# TwoMotorController_1_0.net
KiCad netlist of a schematic drawn in EAGLE
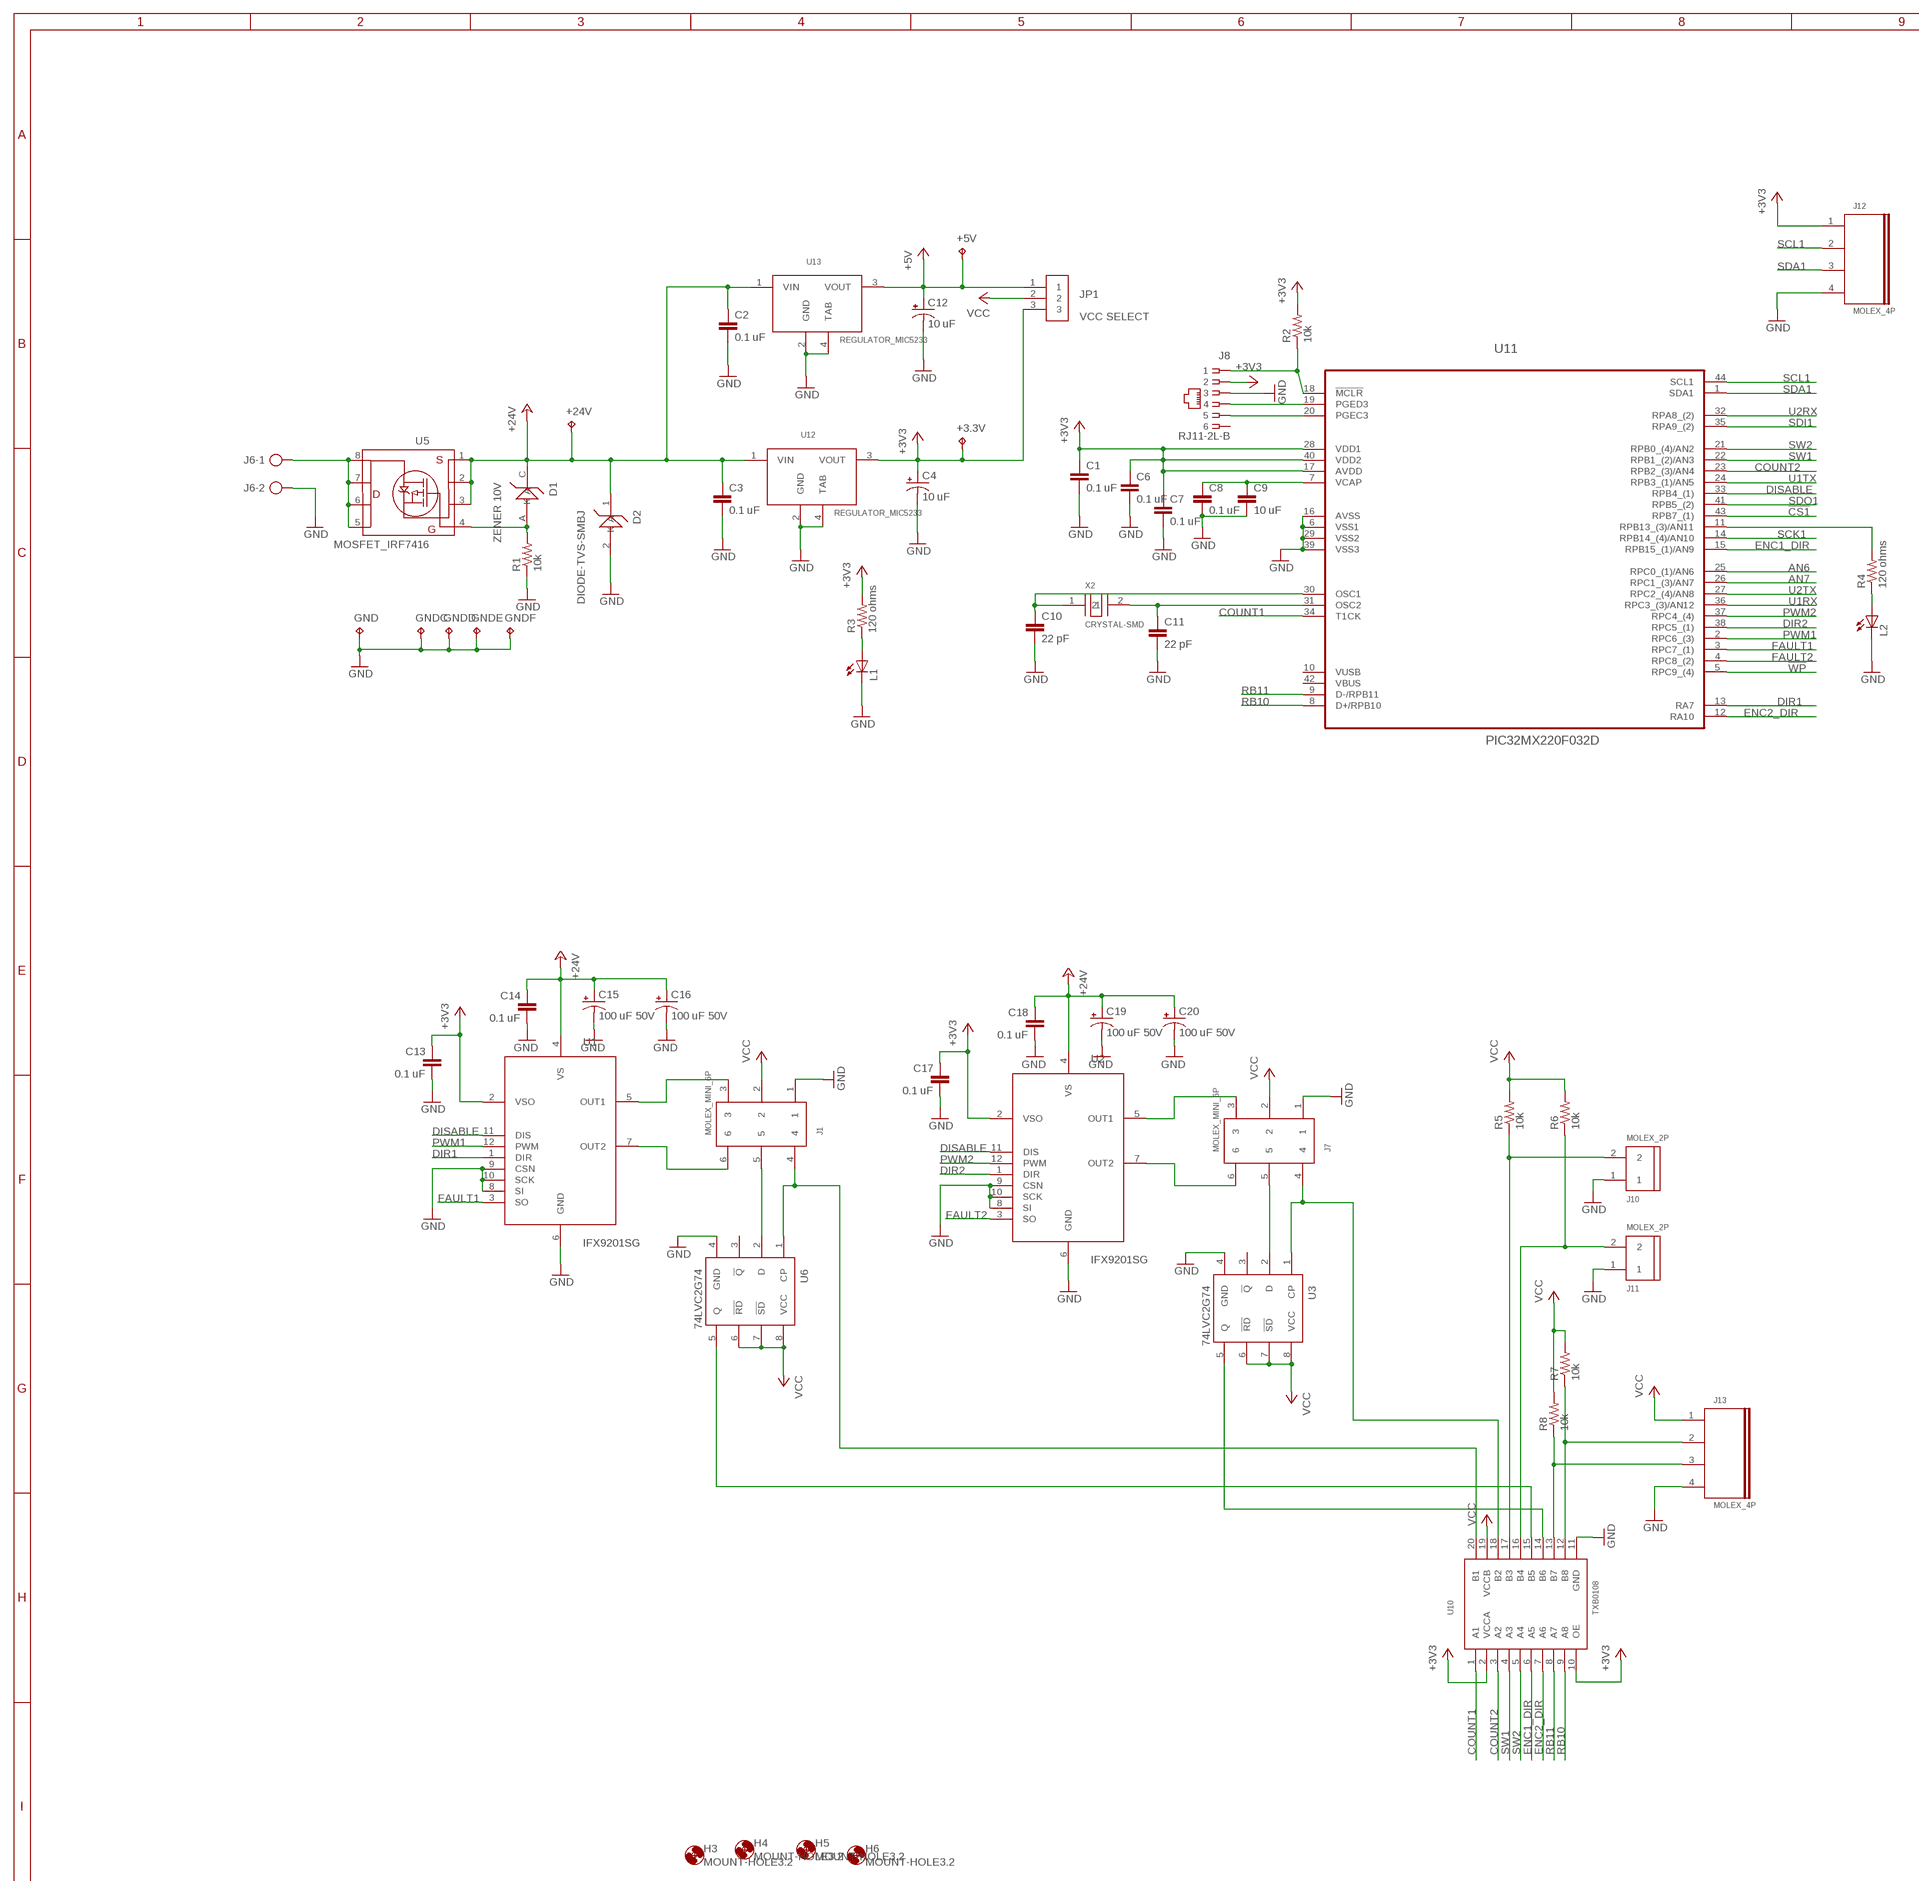
[diagram p0: schematic, sheet 1, part 1 of 2]
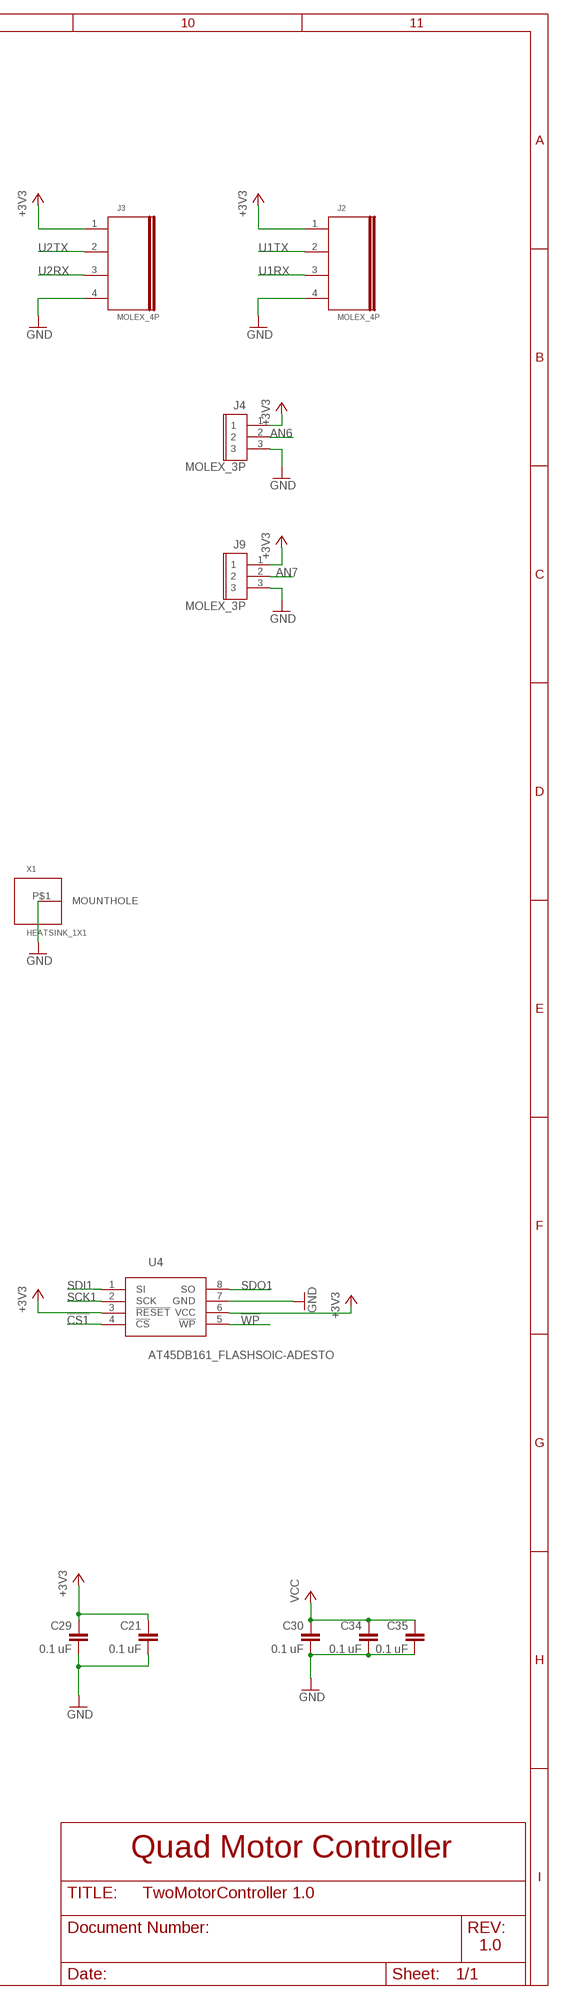
[diagram p1: schematic, sheet 1, part 2 of 2]

(export (version "E")
  (design (tool "Eeschema 10.0.6"))
  (components
    (comp (ref "+3.3V")
      (value "TP")
      (footprint "eagle-import:TESTPAD")
      (libsource (lib "eagle-import") (part "TP"))
    )
    (comp (ref "+5V")
      (value "TP")
      (footprint "eagle-import:TESTPAD")
      (libsource (lib "eagle-import") (part "TP"))
    )
    (comp (ref "+24V")
      (value "TP")
      (footprint "eagle-import:TESTPAD")
      (libsource (lib "eagle-import") (part "TP"))
    )
    (comp (ref "C1")
      (value "0.1 uF")
      (footprint "eagle-import:C0805")
      (libsource (lib "eagle-import") (part "C0805"))
    )
    (comp (ref "C2")
      (value "0.1 uF")
      (footprint "eagle-import:C0805")
      (libsource (lib "eagle-import") (part "C0805"))
    )
    (comp (ref "C3")
      (value "0.1 uF")
      (footprint "eagle-import:C0805")
      (libsource (lib "eagle-import") (part "C0805"))
    )
    (comp (ref "C4")
      (value "10 uF")
      (footprint "eagle-import:POLCAP_2MM")
      (libsource (lib "eagle-import") (part "POLCAPE2-5"))
    )
    (comp (ref "C6")
      (value "0.1 uF")
      (footprint "eagle-import:C0805")
      (libsource (lib "eagle-import") (part "C0805"))
    )
    (comp (ref "C7")
      (value "0.1 uF")
      (footprint "eagle-import:C0805")
      (libsource (lib "eagle-import") (part "C0805"))
    )
    (comp (ref "C8")
      (value "0.1 uF")
      (footprint "eagle-import:C0805")
      (libsource (lib "eagle-import") (part "C0805"))
    )
    (comp (ref "C9")
      (value "10 uF")
      (footprint "eagle-import:C0805")
      (libsource (lib "eagle-import") (part "C0805"))
    )
    (comp (ref "C10")
      (value "22 pF")
      (footprint "eagle-import:C0805")
      (libsource (lib "eagle-import") (part "C0805"))
    )
    (comp (ref "C11")
      (value "22 pF")
      (footprint "eagle-import:C0805")
      (libsource (lib "eagle-import") (part "C0805"))
    )
    (comp (ref "C12")
      (value "10 uF")
      (footprint "eagle-import:POLCAP_2MM")
      (libsource (lib "eagle-import") (part "POLCAPE2-5"))
    )
    (comp (ref "C13")
      (value "0.1 uF")
      (footprint "eagle-import:C0805")
      (libsource (lib "eagle-import") (part "C0805"))
    )
    (comp (ref "C14")
      (value "0.1 uF")
      (footprint "eagle-import:C0805")
      (libsource (lib "eagle-import") (part "C0805"))
    )
    (comp (ref "C15")
      (value "100 uF 50V")
      (footprint "eagle-import:E3,5-10")
      (libsource (lib "eagle-import") (part "POLCAPE3.5-10"))
    )
    (comp (ref "C16")
      (value "100 uF 50V")
      (footprint "eagle-import:E3,5-10")
      (libsource (lib "eagle-import") (part "POLCAPE3.5-10"))
    )
    (comp (ref "C17")
      (value "0.1 uF")
      (footprint "eagle-import:C0805")
      (libsource (lib "eagle-import") (part "C0805"))
    )
    (comp (ref "C18")
      (value "0.1 uF")
      (footprint "eagle-import:C0805")
      (libsource (lib "eagle-import") (part "C0805"))
    )
    (comp (ref "C19")
      (value "100 uF 50V")
      (footprint "eagle-import:E3,5-10")
      (libsource (lib "eagle-import") (part "POLCAPE3.5-10"))
    )
    (comp (ref "C20")
      (value "100 uF 50V")
      (footprint "eagle-import:E3,5-10")
      (libsource (lib "eagle-import") (part "POLCAPE3.5-10"))
    )
    (comp (ref "C21")
      (value "0.1 uF")
      (footprint "eagle-import:C0805")
      (libsource (lib "eagle-import") (part "C0805"))
    )
    (comp (ref "C29")
      (value "0.1 uF")
      (footprint "eagle-import:C0805")
      (libsource (lib "eagle-import") (part "C0805"))
    )
    (comp (ref "C30")
      (value "0.1 uF")
      (footprint "eagle-import:C0805")
      (libsource (lib "eagle-import") (part "C0805"))
    )
    (comp (ref "C34")
      (value "0.1 uF")
      (footprint "eagle-import:C0805")
      (libsource (lib "eagle-import") (part "C0805"))
    )
    (comp (ref "C35")
      (value "0.1 uF")
      (footprint "eagle-import:C0805")
      (libsource (lib "eagle-import") (part "C0805"))
    )
    (comp (ref "D1")
      (value "ZENER 10V")
      (footprint "eagle-import:DO-214AC")
      (libsource (lib "eagle-import") (part "DIODE-ZENERDO-214AC"))
    )
    (comp (ref "D2")
      (value "DIODE-TVS-SMBJ")
      (footprint "eagle-import:DIODE-TVS-SMBJ")
      (libsource (lib "eagle-import") (part "DIODE-TVS-SMBJ"))
    )
    (comp (ref "GND")
      (value "TP")
      (footprint "eagle-import:TESTPAD")
      (libsource (lib "eagle-import") (part "TP"))
    )
    (comp (ref "GNDC")
      (value "TP")
      (footprint "eagle-import:TESTPAD")
      (libsource (lib "eagle-import") (part "TP"))
    )
    (comp (ref "GNDD")
      (value "TP")
      (footprint "eagle-import:TESTPAD")
      (libsource (lib "eagle-import") (part "TP"))
    )
    (comp (ref "GNDE")
      (value "TP")
      (footprint "eagle-import:TESTPAD")
      (libsource (lib "eagle-import") (part "TP"))
    )
    (comp (ref "GNDF")
      (value "TP")
      (footprint "eagle-import:TESTPAD")
      (libsource (lib "eagle-import") (part "TP"))
    )
    (comp (ref "H3")
      (value "MOUNT-HOLE3.2")
      (footprint "eagle-import:3,2")
      (libsource (lib "eagle-import") (part "MOUNT-HOLE3.2"))
    )
    (comp (ref "H4")
      (value "MOUNT-HOLE3.2")
      (footprint "eagle-import:3,2")
      (libsource (lib "eagle-import") (part "MOUNT-HOLE3.2"))
    )
    (comp (ref "H5")
      (value "MOUNT-HOLE3.2")
      (footprint "eagle-import:3,2")
      (libsource (lib "eagle-import") (part "MOUNT-HOLE3.2"))
    )
    (comp (ref "H6")
      (value "MOUNT-HOLE3.2")
      (footprint "eagle-import:3,2")
      (libsource (lib "eagle-import") (part "MOUNT-HOLE3.2"))
    )
    (comp (ref "J1")
      (value "MOLEX_MINI_6P")
      (footprint "eagle-import:MOLEX_MINI_6P")
      (libsource (lib "eagle-import") (part "MOLEX_MINI_6P"))
    )
    (comp (ref "J2")
      (value "MOLEX_4P")
      (footprint "eagle-import:MOLEX_4P")
      (libsource (lib "eagle-import") (part "MOLEX_4P"))
    )
    (comp (ref "J3")
      (value "MOLEX_4P")
      (footprint "eagle-import:MOLEX_4P")
      (libsource (lib "eagle-import") (part "MOLEX_4P"))
    )
    (comp (ref "J4")
      (value "MOLEX_3P")
      (footprint "eagle-import:MOLEX_3P")
      (libsource (lib "eagle-import") (part "MOLEX_3P"))
    )
    (comp (ref "J6")
      (value "TRMBLOCK_5MM_2P")
      (footprint "eagle-import:TRMBLOCK_5MM_2P")
      (libsource (lib "eagle-import") (part "TRMBLOCK_5MM_2P"))
    )
    (comp (ref "J7")
      (value "MOLEX_MINI_6P")
      (footprint "eagle-import:MOLEX_MINI_6P")
      (libsource (lib "eagle-import") (part "MOLEX_MINI_6P"))
    )
    (comp (ref "J8")
      (value "RJ11-2L-B")
      (footprint "eagle-import:RJ11-NO_SHIELD")
      (fields (field (name "MF") "TYCO ELECTRONICS"))
      (libsource (lib "eagle-import") (part "RJ11-2L-B"))
    )
    (comp (ref "J9")
      (value "MOLEX_3P")
      (footprint "eagle-import:MOLEX_3P")
      (libsource (lib "eagle-import") (part "MOLEX_3P"))
    )
    (comp (ref "J10")
      (value "MOLEX_2P")
      (footprint "eagle-import:MOLEX_2P")
      (libsource (lib "eagle-import") (part "MOLEX_2P"))
    )
    (comp (ref "J11")
      (value "MOLEX_2P")
      (footprint "eagle-import:MOLEX_2P")
      (libsource (lib "eagle-import") (part "MOLEX_2P"))
    )
    (comp (ref "J12")
      (value "MOLEX_4P")
      (footprint "eagle-import:MOLEX_4P")
      (libsource (lib "eagle-import") (part "MOLEX_4P"))
    )
    (comp (ref "J13")
      (value "MOLEX_4P")
      (footprint "eagle-import:MOLEX_4P")
      (libsource (lib "eagle-import") (part "MOLEX_4P"))
    )
    (comp (ref "JP1")
      (value "VCC SELECT")
      (footprint "eagle-import:JUMPER_3P")
      (libsource (lib "eagle-import") (part "JUMPER_3P"))
    )
    (comp (ref "L1")
      (value "LED5MM")
      (footprint "eagle-import:LED5MM")
      (libsource (lib "eagle-import") (part "LED5MM"))
    )
    (comp (ref "L2")
      (value "LED5MM")
      (footprint "eagle-import:LED5MM")
      (libsource (lib "eagle-import") (part "LED5MM"))
    )
    (comp (ref "R1")
      (value "10k")
      (footprint "eagle-import:R0805")
      (libsource (lib "eagle-import") (part "RESISTORR0805"))
    )
    (comp (ref "R2")
      (value "10k")
      (footprint "eagle-import:R0805")
      (libsource (lib "eagle-import") (part "RESISTORR0805"))
    )
    (comp (ref "R3")
      (value "120 ohms")
      (footprint "eagle-import:R0805")
      (libsource (lib "eagle-import") (part "RESISTORR0805"))
    )
    (comp (ref "R4")
      (value "120 ohms")
      (footprint "eagle-import:R0805")
      (libsource (lib "eagle-import") (part "RESISTORR0805"))
    )
    (comp (ref "R5")
      (value "10k")
      (footprint "eagle-import:R0805")
      (libsource (lib "eagle-import") (part "RESISTORR0805"))
    )
    (comp (ref "R6")
      (value "10k")
      (footprint "eagle-import:R0805")
      (libsource (lib "eagle-import") (part "RESISTORR0805"))
    )
    (comp (ref "R7")
      (value "10k")
      (footprint "eagle-import:R0805")
      (libsource (lib "eagle-import") (part "RESISTORR0805"))
    )
    (comp (ref "R8")
      (value "10k")
      (footprint "eagle-import:R0805")
      (libsource (lib "eagle-import") (part "RESISTORR0805"))
    )
    (comp (ref "U1")
      (value "IFX9201SG")
      (footprint "eagle-import:IFX9201SG")
      (libsource (lib "eagle-import") (part "IFX9201SG"))
    )
    (comp (ref "U2")
      (value "IFX9201SG")
      (footprint "eagle-import:IFX9201SG")
      (libsource (lib "eagle-import") (part "IFX9201SG"))
    )
    (comp (ref "U3")
      (value "74LVC2G74")
      (footprint "eagle-import:TSSOP8")
      (libsource (lib "eagle-import") (part "74LVC2G74"))
    )
    (comp (ref "U4")
      (value "AT45DB161_FLASHSOIC-ADESTO")
      (footprint "eagle-import:SOIC-ADESTO")
      (libsource (lib "eagle-import") (part "AT45DB161_FLASHSOIC-ADESTO"))
    )
    (comp (ref "U5")
      (value "MOSFET_IRF7416")
      (footprint "eagle-import:SO-8-3.9MM")
      (libsource (lib "eagle-import") (part "MOSFET_IRF7416"))
    )
    (comp (ref "U6")
      (value "74LVC2G74")
      (footprint "eagle-import:TSSOP8")
      (libsource (lib "eagle-import") (part "74LVC2G74"))
    )
    (comp (ref "U10")
      (value "TXB0108")
      (footprint "eagle-import:TSSOP20")
      (libsource (lib "eagle-import") (part "TXB0108"))
    )
    (comp (ref "U11")
      (value "PIC32MX220F032D")
      (footprint "eagle-import:QFP80P1200X1200X120-44N")
      (fields (field (name "MPN") "PIC18F4550-I/PT"))
      (libsource (lib "eagle-import") (part "PIC32MX220F032D"))
    )
    (comp (ref "U12")
      (value "REGULATOR_MIC5233")
      (footprint "eagle-import:REGULATOR_MIC5233")
      (libsource (lib "eagle-import") (part "REGULATOR_MIC5233"))
    )
    (comp (ref "U13")
      (value "REGULATOR_MIC5233")
      (footprint "eagle-import:REGULATOR_MIC5233")
      (libsource (lib "eagle-import") (part "REGULATOR_MIC5233"))
    )
    (comp (ref "X1")
      (value "HEATSINK_1X1")
      (footprint "eagle-import:HEATSINK_1X1")
      (libsource (lib "eagle-import") (part "HEATSINK_1X1"))
    )
    (comp (ref "X2")
      (value "CRYSTAL-SMD")
      (footprint "eagle-import:CRYSTAL-SMD")
      (libsource (lib "eagle-import") (part "CRYSTAL-SMD"))
    )
  )
  (nets
    (net (code "1") (name "+3V3") (class "Default")
      (node (ref "+3.3V") (pin "P$1") (pinfunction "TP_P$1") (pintype "input"))
      (node (ref "C1") (pin "1") (pinfunction "1_1") (pintype "passive"))
      (node (ref "C13") (pin "1") (pinfunction "1_1") (pintype "passive"))
      (node (ref "C17") (pin "1") (pinfunction "1_1") (pintype "passive"))
      (node (ref "C21") (pin "1") (pinfunction "1_1") (pintype "passive"))
      (node (ref "C29") (pin "1") (pinfunction "1_1") (pintype "passive"))
      (node (ref "C4") (pin "+") (pinfunction "+_+") (pintype "passive"))
      (node (ref "C6") (pin "1") (pinfunction "1_1") (pintype "passive"))
      (node (ref "C7") (pin "1") (pinfunction "1_1") (pintype "passive"))
      (node (ref "J12") (pin "1") (pinfunction "1_1") (pintype "bidirectional"))
      (node (ref "J2") (pin "1") (pinfunction "1_1") (pintype "bidirectional"))
      (node (ref "J3") (pin "1") (pinfunction "1_1") (pintype "bidirectional"))
      (node (ref "J4") (pin "1") (pinfunction "1_1") (pintype "bidirectional"))
      (node (ref "J8") (pin "2") (pinfunction "2_2") (pintype "passive"))
      (node (ref "J9") (pin "1") (pinfunction "1_1") (pintype "bidirectional"))
      (node (ref "JP1") (pin "3") (pinfunction "3_3") (pintype "bidirectional"))
      (node (ref "R2") (pin "2") (pinfunction "2_2") (pintype "passive"))
      (node (ref "R3") (pin "2") (pinfunction "2_2") (pintype "passive"))
      (node (ref "U1") (pin "2") (pinfunction "VSO_2") (pintype "bidirectional"))
      (node (ref "U10") (pin "10") (pinfunction "OE_10") (pintype "bidirectional"))
      (node (ref "U10") (pin "2") (pinfunction "VCCA_2") (pintype "bidirectional"))
      (node (ref "U11") (pin "17") (pinfunction "AVDD_17") (pintype "power_in"))
      (node (ref "U11") (pin "28") (pinfunction "VDD1_28") (pintype "power_in"))
      (node (ref "U11") (pin "40") (pinfunction "VDD2_40") (pintype "input"))
      (node (ref "U12") (pin "3") (pinfunction "VOUT_3") (pintype "power_in"))
      (node (ref "U2") (pin "2") (pinfunction "VSO_2") (pintype "bidirectional"))
      (node (ref "U4") (pin "3") (pinfunction "~{RESET}_3") (pintype "input"))
      (node (ref "U4") (pin "6") (pinfunction "VCC_6") (pintype "power_in"))
    )
    (net (code "2") (name "+5V") (class "Default")
      (node (ref "+5V") (pin "P$1") (pinfunction "TP_P$1") (pintype "input"))
      (node (ref "C12") (pin "+") (pinfunction "+_+") (pintype "passive"))
      (node (ref "JP1") (pin "1") (pinfunction "1_1") (pintype "bidirectional"))
      (node (ref "U13") (pin "3") (pinfunction "VOUT_3") (pintype "power_in"))
    )
    (net (code "3") (name "+24V") (class "Default")
      (node (ref "+24V") (pin "P$1") (pinfunction "TP_P$1") (pintype "input"))
      (node (ref "C14") (pin "1") (pinfunction "1_1") (pintype "passive"))
      (node (ref "C15") (pin "+") (pinfunction "+_+") (pintype "passive"))
      (node (ref "C16") (pin "+") (pinfunction "+_+") (pintype "passive"))
      (node (ref "C18") (pin "1") (pinfunction "1_1") (pintype "passive"))
      (node (ref "C19") (pin "+") (pinfunction "+_+") (pintype "passive"))
      (node (ref "C2") (pin "1") (pinfunction "1_1") (pintype "passive"))
      (node (ref "C20") (pin "+") (pinfunction "+_+") (pintype "passive"))
      (node (ref "C3") (pin "1") (pinfunction "1_1") (pintype "passive"))
      (node (ref "D1") (pin "C") (pinfunction "K_C") (pintype "power_in"))
      (node (ref "D2") (pin "1") (pinfunction "K_1") (pintype "power_in"))
      (node (ref "U1") (pin "4") (pinfunction "VS_4") (pintype "power_in"))
      (node (ref "U12") (pin "1") (pinfunction "VIN_1") (pintype "power_in"))
      (node (ref "U13") (pin "1") (pinfunction "VIN_1") (pintype "power_in"))
      (node (ref "U2") (pin "4") (pinfunction "VS_4") (pintype "power_in"))
      (node (ref "U5") (pin "1") (pinfunction "P$1_1") (pintype "bidirectional"))
      (node (ref "U5") (pin "2") (pinfunction "P$2_2") (pintype "bidirectional"))
      (node (ref "U5") (pin "3") (pinfunction "P$3_3") (pintype "bidirectional"))
    )
    (net (code "4") (name "/AN6") (class "Default")
      (node (ref "J4") (pin "2") (pinfunction "2_2") (pintype "bidirectional"))
      (node (ref "U11") (pin "25") (pinfunction "RPC0_(1)/AN6_25") (pintype "bidirectional"))
    )
    (net (code "5") (name "/AN7") (class "Default")
      (node (ref "J9") (pin "2") (pinfunction "2_2") (pintype "bidirectional"))
      (node (ref "U11") (pin "26") (pinfunction "RPC1_(3)/AN7_26") (pintype "bidirectional"))
    )
    (net (code "6") (name "/COUNT1") (class "Default")
      (node (ref "U10") (pin "1") (pinfunction "A1_1") (pintype "bidirectional"))
      (node (ref "U11") (pin "34") (pinfunction "T1CK_34") (pintype "bidirectional"))
    )
    (net (code "7") (name "/COUNT2") (class "Default")
      (node (ref "U10") (pin "3") (pinfunction "A2_3") (pintype "bidirectional"))
      (node (ref "U11") (pin "23") (pinfunction "RPB2_(3)/AN4_23") (pintype "bidirectional"))
    )
    (net (code "8") (name "/DIR1") (class "Default")
      (node (ref "U1") (pin "1") (pinfunction "DIR_1") (pintype "input"))
      (node (ref "U11") (pin "13") (pinfunction "RA7_13") (pintype "bidirectional"))
    )
    (net (code "9") (name "/DIR2") (class "Default")
      (node (ref "U11") (pin "38") (pinfunction "RPC5_(1)_38") (pintype "bidirectional"))
      (node (ref "U2") (pin "1") (pinfunction "DIR_1") (pintype "input"))
    )
    (net (code "10") (name "/DISABLE") (class "Default")
      (node (ref "U1") (pin "11") (pinfunction "DIS_11") (pintype "input"))
      (node (ref "U11") (pin "33") (pinfunction "RPB4_(1)_33") (pintype "bidirectional"))
      (node (ref "U2") (pin "11") (pinfunction "DIS_11") (pintype "input"))
    )
    (net (code "11") (name "/ENC1_DIR") (class "Default")
      (node (ref "U10") (pin "6") (pinfunction "A5_6") (pintype "bidirectional"))
      (node (ref "U11") (pin "15") (pinfunction "RPB15_(1)/AN9_15") (pintype "bidirectional"))
    )
    (net (code "12") (name "/ENC2_DIR") (class "Default")
      (node (ref "U10") (pin "7") (pinfunction "A6_7") (pintype "bidirectional"))
      (node (ref "U11") (pin "12") (pinfunction "RA10_12") (pintype "bidirectional"))
    )
    (net (code "13") (name "/FAULT1") (class "Default")
      (node (ref "U1") (pin "3") (pinfunction "SO_3") (pintype "output"))
      (node (ref "U11") (pin "3") (pinfunction "RPC7_(1)_3") (pintype "bidirectional"))
    )
    (net (code "14") (name "/FAULT2") (class "Default")
      (node (ref "U11") (pin "4") (pinfunction "RPC8_(2)_4") (pintype "bidirectional"))
      (node (ref "U2") (pin "3") (pinfunction "SO_3") (pintype "output"))
    )
    (net (code "15") (name "/PWM1") (class "Default")
      (node (ref "U1") (pin "12") (pinfunction "PWM_12") (pintype "input"))
      (node (ref "U11") (pin "2") (pinfunction "RPC6_(3)_2") (pintype "bidirectional"))
    )
    (net (code "16") (name "/PWM2") (class "Default")
      (node (ref "U11") (pin "37") (pinfunction "RPC4_(4)_37") (pintype "bidirectional"))
      (node (ref "U2") (pin "12") (pinfunction "PWM_12") (pintype "input"))
    )
    (net (code "17") (name "/RB10") (class "Default")
      (node (ref "U10") (pin "9") (pinfunction "A8_9") (pintype "bidirectional"))
      (node (ref "U11") (pin "8") (pinfunction "D+/RPB10_8") (pintype "bidirectional"))
    )
    (net (code "18") (name "/RB11") (class "Default")
      (node (ref "U10") (pin "8") (pinfunction "A7_8") (pintype "bidirectional"))
      (node (ref "U11") (pin "9") (pinfunction "D-/RPB11_9") (pintype "bidirectional"))
    )
    (net (code "19") (name "/SCK1") (class "Default")
      (node (ref "U11") (pin "14") (pinfunction "RPB14_(4)/AN10_14") (pintype "bidirectional"))
      (node (ref "U4") (pin "2") (pinfunction "SCK_2") (pintype "input"))
    )
    (net (code "20") (name "/SCL1") (class "Default")
      (node (ref "J12") (pin "2") (pinfunction "2_2") (pintype "bidirectional"))
      (node (ref "U11") (pin "44") (pinfunction "SCL1_44") (pintype "bidirectional"))
    )
    (net (code "21") (name "/SDA1") (class "Default")
      (node (ref "J12") (pin "3") (pinfunction "3_3") (pintype "bidirectional"))
      (node (ref "U11") (pin "1") (pinfunction "SDA1_1") (pintype "bidirectional"))
    )
    (net (code "22") (name "/SDI1") (class "Default")
      (node (ref "U11") (pin "35") (pinfunction "RPA9_(2)_35") (pintype "bidirectional"))
      (node (ref "U4") (pin "1") (pinfunction "SI_1") (pintype "input"))
    )
    (net (code "23") (name "/SDO1") (class "Default")
      (node (ref "U11") (pin "41") (pinfunction "RPB5_(2)_41") (pintype "bidirectional"))
      (node (ref "U4") (pin "8") (pinfunction "SO_8") (pintype "output"))
    )
    (net (code "24") (name "/SW1") (class "Default")
      (node (ref "U10") (pin "4") (pinfunction "A3_4") (pintype "bidirectional"))
      (node (ref "U11") (pin "22") (pinfunction "RPB1_(2)/AN3_22") (pintype "bidirectional"))
    )
    (net (code "25") (name "/SW2") (class "Default")
      (node (ref "U10") (pin "5") (pinfunction "A4_5") (pintype "bidirectional"))
      (node (ref "U11") (pin "21") (pinfunction "RPB0_(4)/AN2_21") (pintype "bidirectional"))
    )
    (net (code "26") (name "/U1RX") (class "Default")
      (node (ref "J2") (pin "3") (pinfunction "3_3") (pintype "bidirectional"))
      (node (ref "U11") (pin "36") (pinfunction "RPC3_(3)/AN12_36") (pintype "bidirectional"))
    )
    (net (code "27") (name "/U1TX") (class "Default")
      (node (ref "J2") (pin "2") (pinfunction "2_2") (pintype "bidirectional"))
      (node (ref "U11") (pin "24") (pinfunction "RPB3_(1)/AN5_24") (pintype "bidirectional"))
    )
    (net (code "28") (name "/U2RX") (class "Default")
      (node (ref "J3") (pin "3") (pinfunction "3_3") (pintype "bidirectional"))
      (node (ref "U11") (pin "32") (pinfunction "RPA8_(2)_32") (pintype "bidirectional"))
    )
    (net (code "29") (name "/U2TX") (class "Default")
      (node (ref "J3") (pin "2") (pinfunction "2_2") (pintype "bidirectional"))
      (node (ref "U11") (pin "27") (pinfunction "RPC2_(4)/AN8_27") (pintype "bidirectional"))
    )
    (net (code "30") (name "/~{CS1}") (class "Default")
      (node (ref "U11") (pin "43") (pinfunction "RPB7_(1)_43") (pintype "bidirectional"))
      (node (ref "U4") (pin "4") (pinfunction "~{CS}_4") (pintype "input"))
    )
    (net (code "31") (name "/~{WP}") (class "Default")
      (node (ref "U11") (pin "5") (pinfunction "RPC9_(4)_5") (pintype "bidirectional"))
      (node (ref "U4") (pin "5") (pinfunction "~{WP}_5") (pintype "input"))
    )
    (net (code "32") (name "GND") (class "Default")
      (node (ref "C1") (pin "2") (pinfunction "2_2") (pintype "passive"))
      (node (ref "C10") (pin "2") (pinfunction "2_2") (pintype "passive"))
      (node (ref "C11") (pin "2") (pinfunction "2_2") (pintype "passive"))
      (node (ref "C12") (pin "-") (pinfunction "-_-") (pintype "passive"))
      (node (ref "C13") (pin "2") (pinfunction "2_2") (pintype "passive"))
      (node (ref "C14") (pin "2") (pinfunction "2_2") (pintype "passive"))
      (node (ref "C15") (pin "-") (pinfunction "-_-") (pintype "passive"))
      (node (ref "C16") (pin "-") (pinfunction "-_-") (pintype "passive"))
      (node (ref "C17") (pin "2") (pinfunction "2_2") (pintype "passive"))
      (node (ref "C18") (pin "2") (pinfunction "2_2") (pintype "passive"))
      (node (ref "C19") (pin "-") (pinfunction "-_-") (pintype "passive"))
      (node (ref "C2") (pin "2") (pinfunction "2_2") (pintype "passive"))
      (node (ref "C20") (pin "-") (pinfunction "-_-") (pintype "passive"))
      (node (ref "C21") (pin "2") (pinfunction "2_2") (pintype "passive"))
      (node (ref "C29") (pin "2") (pinfunction "2_2") (pintype "passive"))
      (node (ref "C3") (pin "2") (pinfunction "2_2") (pintype "passive"))
      (node (ref "C30") (pin "2") (pinfunction "2_2") (pintype "passive"))
      (node (ref "C34") (pin "2") (pinfunction "2_2") (pintype "passive"))
      (node (ref "C35") (pin "2") (pinfunction "2_2") (pintype "passive"))
      (node (ref "C4") (pin "-") (pinfunction "-_-") (pintype "passive"))
      (node (ref "C6") (pin "2") (pinfunction "2_2") (pintype "passive"))
      (node (ref "C7") (pin "2") (pinfunction "2_2") (pintype "passive"))
      (node (ref "C8") (pin "2") (pinfunction "2_2") (pintype "passive"))
      (node (ref "C9") (pin "2") (pinfunction "2_2") (pintype "passive"))
      (node (ref "D2") (pin "2") (pinfunction "A_2") (pintype "power_in"))
      (node (ref "GND") (pin "P$1") (pinfunction "TP_P$1") (pintype "input"))
      (node (ref "GNDC") (pin "P$1") (pinfunction "TP_P$1") (pintype "input"))
      (node (ref "GNDD") (pin "P$1") (pinfunction "TP_P$1") (pintype "input"))
      (node (ref "GNDE") (pin "P$1") (pinfunction "TP_P$1") (pintype "input"))
      (node (ref "GNDF") (pin "P$1") (pinfunction "TP_P$1") (pintype "input"))
      (node (ref "J1") (pin "1") (pinfunction "1_1") (pintype "bidirectional"))
      (node (ref "J10") (pin "1") (pinfunction "1_1") (pintype "bidirectional"))
      (node (ref "J11") (pin "1") (pinfunction "1_1") (pintype "bidirectional"))
      (node (ref "J12") (pin "4") (pinfunction "4_4") (pintype "bidirectional"))
      (node (ref "J13") (pin "4") (pinfunction "4_4") (pintype "bidirectional"))
      (node (ref "J2") (pin "4") (pinfunction "4_4") (pintype "bidirectional"))
      (node (ref "J3") (pin "4") (pinfunction "4_4") (pintype "bidirectional"))
      (node (ref "J4") (pin "3") (pinfunction "3_3") (pintype "bidirectional"))
      (node (ref "J6") (pin "2") (pinfunction "KL_2") (pintype "passive"))
      (node (ref "J7") (pin "1") (pinfunction "1_1") (pintype "bidirectional"))
      (node (ref "J8") (pin "3") (pinfunction "3_3") (pintype "passive"))
      (node (ref "J9") (pin "3") (pinfunction "3_3") (pintype "bidirectional"))
      (node (ref "L1") (pin "K") (pinfunction "C_K") (pintype "passive"))
      (node (ref "L2") (pin "K") (pinfunction "C_K") (pintype "passive"))
      (node (ref "R1") (pin "1") (pinfunction "1_1") (pintype "passive"))
      (node (ref "U1") (pin "10") (pinfunction "SCK_10") (pintype "input"))
      (node (ref "U1") (pin "6") (pinfunction "GND_6") (pintype "power_in"))
      (node (ref "U1") (pin "8") (pinfunction "SI_8") (pintype "input"))
      (node (ref "U1") (pin "9") (pinfunction "CSN_9") (pintype "input"))
      (node (ref "U10") (pin "11") (pinfunction "GND_11") (pintype "bidirectional"))
      (node (ref "U11") (pin "16") (pinfunction "AVSS_16") (pintype "bidirectional"))
      (node (ref "U11") (pin "29") (pinfunction "VSS2_29") (pintype "bidirectional"))
      (node (ref "U11") (pin "39") (pinfunction "VSS3_39") (pintype "bidirectional"))
      (node (ref "U11") (pin "6") (pinfunction "VSS1_6") (pintype "bidirectional"))
      (node (ref "U12") (pin "2") (pinfunction "GND_2") (pintype "power_in"))
      (node (ref "U12") (pin "4") (pinfunction "TAB_4") (pintype "power_in"))
      (node (ref "U13") (pin "2") (pinfunction "GND_2") (pintype "power_in"))
      (node (ref "U13") (pin "4") (pinfunction "TAB_4") (pintype "power_in"))
      (node (ref "U2") (pin "10") (pinfunction "SCK_10") (pintype "input"))
      (node (ref "U2") (pin "6") (pinfunction "GND_6") (pintype "power_in"))
      (node (ref "U2") (pin "8") (pinfunction "SI_8") (pintype "input"))
      (node (ref "U2") (pin "9") (pinfunction "CSN_9") (pintype "input"))
      (node (ref "U3") (pin "4") (pinfunction "GND_4") (pintype "power_in"))
      (node (ref "U4") (pin "7") (pinfunction "GND_7") (pintype "power_in"))
      (node (ref "U6") (pin "4") (pinfunction "GND_4") (pintype "power_in"))
      (node (ref "X1") (pin "P$1") (pinfunction "MOUNTHOLE_P$1") (pintype "bidirectional"))
    )
    (net (code "33") (name "Net-(J6A-KL)") (class "Default")
      (node (ref "J6") (pin "1") (pinfunction "KL_1") (pintype "passive"))
      (node (ref "U5") (pin "5") (pinfunction "P$5_5") (pintype "bidirectional"))
      (node (ref "U5") (pin "6") (pinfunction "P$6_6") (pintype "bidirectional"))
      (node (ref "U5") (pin "7") (pinfunction "P$7_7") (pintype "bidirectional"))
      (node (ref "U5") (pin "8") (pinfunction "P$8_8") (pintype "bidirectional"))
    )
    (net (code "34") (name "Net-(L1-PadA)") (class "Default")
      (node (ref "L1") (pin "A") (pinfunction "A_A") (pintype "passive"))
      (node (ref "R3") (pin "1") (pinfunction "1_1") (pintype "passive"))
    )
    (net (code "35") (name "Net-(L2-PadA)") (class "Default")
      (node (ref "L2") (pin "A") (pinfunction "A_A") (pintype "passive"))
      (node (ref "R4") (pin "1") (pinfunction "1_1") (pintype "passive"))
    )
    (net (code "36") (name "Net-(U1-OUT1)") (class "Default")
      (node (ref "J1") (pin "3") (pinfunction "3_3") (pintype "bidirectional"))
      (node (ref "U1") (pin "5") (pinfunction "OUT1_5") (pintype "output"))
    )
    (net (code "37") (name "Net-(U1-OUT2)") (class "Default")
      (node (ref "J1") (pin "6") (pinfunction "6_6") (pintype "bidirectional"))
      (node (ref "U1") (pin "7") (pinfunction "OUT2_7") (pintype "output"))
    )
    (net (code "38") (name "Net-(U2-OUT1)") (class "Default")
      (node (ref "J7") (pin "3") (pinfunction "3_3") (pintype "bidirectional"))
      (node (ref "U2") (pin "5") (pinfunction "OUT1_5") (pintype "output"))
    )
    (net (code "39") (name "Net-(U2-OUT2)") (class "Default")
      (node (ref "J7") (pin "6") (pinfunction "6_6") (pintype "bidirectional"))
      (node (ref "U2") (pin "7") (pinfunction "OUT2_7") (pintype "output"))
    )
    (net (code "40") (name "Net-(U3-D)") (class "Default")
      (node (ref "J7") (pin "5") (pinfunction "5_5") (pintype "bidirectional"))
      (node (ref "U3") (pin "2") (pinfunction "D_2") (pintype "input"))
    )
    (net (code "41") (name "Net-(U5-P$4)") (class "Default")
      (node (ref "D1") (pin "A") (pinfunction "A_A") (pintype "power_in"))
      (node (ref "R1") (pin "2") (pinfunction "2_2") (pintype "passive"))
      (node (ref "U5") (pin "4") (pinfunction "P$4_4") (pintype "bidirectional"))
    )
    (net (code "42") (name "Net-(U6-D)") (class "Default")
      (node (ref "J1") (pin "5") (pinfunction "5_5") (pintype "bidirectional"))
      (node (ref "U6") (pin "2") (pinfunction "D_2") (pintype "input"))
    )
    (net (code "43") (name "Net-(U10-B1)") (class "Default")
      (node (ref "J1") (pin "4") (pinfunction "4_4") (pintype "bidirectional"))
      (node (ref "U10") (pin "20") (pinfunction "B1_20") (pintype "bidirectional"))
      (node (ref "U6") (pin "1") (pinfunction "CP_1") (pintype "input"))
    )
    (net (code "44") (name "Net-(U10-B2)") (class "Default")
      (node (ref "J7") (pin "4") (pinfunction "4_4") (pintype "bidirectional"))
      (node (ref "U10") (pin "18") (pinfunction "B2_18") (pintype "bidirectional"))
      (node (ref "U3") (pin "1") (pinfunction "CP_1") (pintype "input"))
    )
    (net (code "45") (name "Net-(U10-B3)") (class "Default")
      (node (ref "J10") (pin "2") (pinfunction "2_2") (pintype "bidirectional"))
      (node (ref "R5") (pin "1") (pinfunction "1_1") (pintype "passive"))
      (node (ref "U10") (pin "17") (pinfunction "B3_17") (pintype "bidirectional"))
    )
    (net (code "46") (name "Net-(U10-B4)") (class "Default")
      (node (ref "J11") (pin "2") (pinfunction "2_2") (pintype "bidirectional"))
      (node (ref "R6") (pin "1") (pinfunction "1_1") (pintype "passive"))
      (node (ref "U10") (pin "16") (pinfunction "B4_16") (pintype "bidirectional"))
    )
    (net (code "47") (name "Net-(U10-B5)") (class "Default")
      (node (ref "U10") (pin "15") (pinfunction "B5_15") (pintype "bidirectional"))
      (node (ref "U6") (pin "5") (pinfunction "Q_5") (pintype "output"))
    )
    (net (code "48") (name "Net-(U10-B6)") (class "Default")
      (node (ref "U10") (pin "14") (pinfunction "B6_14") (pintype "bidirectional"))
      (node (ref "U3") (pin "5") (pinfunction "Q_5") (pintype "output"))
    )
    (net (code "49") (name "Net-(U10-B7)") (class "Default")
      (node (ref "J13") (pin "3") (pinfunction "3_3") (pintype "bidirectional"))
      (node (ref "R8") (pin "1") (pinfunction "1_1") (pintype "passive"))
      (node (ref "U10") (pin "13") (pinfunction "B7_13") (pintype "bidirectional"))
    )
    (net (code "50") (name "Net-(U10-B8)") (class "Default")
      (node (ref "J13") (pin "2") (pinfunction "2_2") (pintype "bidirectional"))
      (node (ref "R7") (pin "1") (pinfunction "1_1") (pintype "passive"))
      (node (ref "U10") (pin "12") (pinfunction "B8_12") (pintype "bidirectional"))
    )
    (net (code "51") (name "Net-(U11-OSC1)") (class "Default")
      (node (ref "C10") (pin "1") (pinfunction "1_1") (pintype "passive"))
      (node (ref "U11") (pin "30") (pinfunction "OSC1_30") (pintype "bidirectional"))
      (node (ref "X2") (pin "1") (pinfunction "1_1") (pintype "bidirectional"))
    )
    (net (code "52") (name "Net-(U11-OSC2)") (class "Default")
      (node (ref "C11") (pin "1") (pinfunction "1_1") (pintype "passive"))
      (node (ref "U11") (pin "31") (pinfunction "OSC2_31") (pintype "bidirectional"))
      (node (ref "X2") (pin "2") (pinfunction "2_2") (pintype "bidirectional"))
    )
    (net (code "53") (name "Net-(U11-PGEC3)") (class "Default")
      (node (ref "J8") (pin "5") (pinfunction "5_5") (pintype "passive"))
      (node (ref "U11") (pin "20") (pinfunction "PGEC3_20") (pintype "bidirectional"))
    )
    (net (code "54") (name "Net-(U11-PGED3)") (class "Default")
      (node (ref "J8") (pin "4") (pinfunction "4_4") (pintype "passive"))
      (node (ref "U11") (pin "19") (pinfunction "PGED3_19") (pintype "bidirectional"))
    )
    (net (code "55") (name "Net-(U11-RPB13_(3){slash}AN11)") (class "Default")
      (node (ref "R4") (pin "2") (pinfunction "2_2") (pintype "passive"))
      (node (ref "U11") (pin "11") (pinfunction "RPB13_(3)/AN11_11") (pintype "bidirectional"))
    )
    (net (code "56") (name "Net-(U11-VCAP)") (class "Default")
      (node (ref "C8") (pin "1") (pinfunction "1_1") (pintype "passive"))
      (node (ref "C9") (pin "1") (pinfunction "1_1") (pintype "passive"))
      (node (ref "U11") (pin "7") (pinfunction "VCAP_7") (pintype "bidirectional"))
    )
    (net (code "57") (name "Net-(U11-~{MCLR})") (class "Default")
      (node (ref "J8") (pin "1") (pinfunction "1_1") (pintype "passive"))
      (node (ref "R2") (pin "1") (pinfunction "1_1") (pintype "passive"))
      (node (ref "U11") (pin "18") (pinfunction "~{MCLR}_18") (pintype "power_in"))
    )
    (net (code "58") (name "VCC") (class "Default")
      (node (ref "C30") (pin "1") (pinfunction "1_1") (pintype "passive"))
      (node (ref "C34") (pin "1") (pinfunction "1_1") (pintype "passive"))
      (node (ref "C35") (pin "1") (pinfunction "1_1") (pintype "passive"))
      (node (ref "J1") (pin "2") (pinfunction "2_2") (pintype "bidirectional"))
      (node (ref "J13") (pin "1") (pinfunction "1_1") (pintype "bidirectional"))
      (node (ref "J7") (pin "2") (pinfunction "2_2") (pintype "bidirectional"))
      (node (ref "JP1") (pin "2") (pinfunction "2_2") (pintype "bidirectional"))
      (node (ref "R5") (pin "2") (pinfunction "2_2") (pintype "passive"))
      (node (ref "R6") (pin "2") (pinfunction "2_2") (pintype "passive"))
      (node (ref "R7") (pin "2") (pinfunction "2_2") (pintype "passive"))
      (node (ref "R8") (pin "2") (pinfunction "2_2") (pintype "passive"))
      (node (ref "U10") (pin "19") (pinfunction "VCCB_19") (pintype "bidirectional"))
      (node (ref "U3") (pin "6") (pinfunction "~{RD}_6") (pintype "input"))
      (node (ref "U3") (pin "7") (pinfunction "~{SD}_7") (pintype "input"))
      (node (ref "U3") (pin "8") (pinfunction "VCC_8") (pintype "power_in"))
      (node (ref "U6") (pin "6") (pinfunction "~{RD}_6") (pintype "input"))
      (node (ref "U6") (pin "7") (pinfunction "~{SD}_7") (pintype "input"))
      (node (ref "U6") (pin "8") (pinfunction "VCC_8") (pintype "power_in"))
    )
    (net (code "59") (name "unconnected-(J8-Pad6)") (class "Default")
      (node (ref "J8") (pin "6") (pinfunction "6_6") (pintype "passive"))
    )
    (net (code "60") (name "unconnected-(U3-~{Q}-Pad3)") (class "Default")
      (node (ref "U3") (pin "3") (pinfunction "~{Q}_3") (pintype "output"))
    )
    (net (code "61") (name "unconnected-(U6-~{Q}-Pad3)") (class "Default")
      (node (ref "U6") (pin "3") (pinfunction "~{Q}_3") (pintype "output"))
    )
    (net (code "62") (name "unconnected-(U11-VBUS-Pad42)") (class "Default")
      (node (ref "U11") (pin "42") (pinfunction "VBUS_42") (pintype "bidirectional"))
    )
    (net (code "63") (name "unconnected-(U11-VUSB-Pad10)") (class "Default")
      (node (ref "U11") (pin "10") (pinfunction "VUSB_10") (pintype "bidirectional"))
    )
  )
)
